# DC-DC_Module_Board_Mk_2.net
KiCad netlist of a schematic drawn in EAGLE
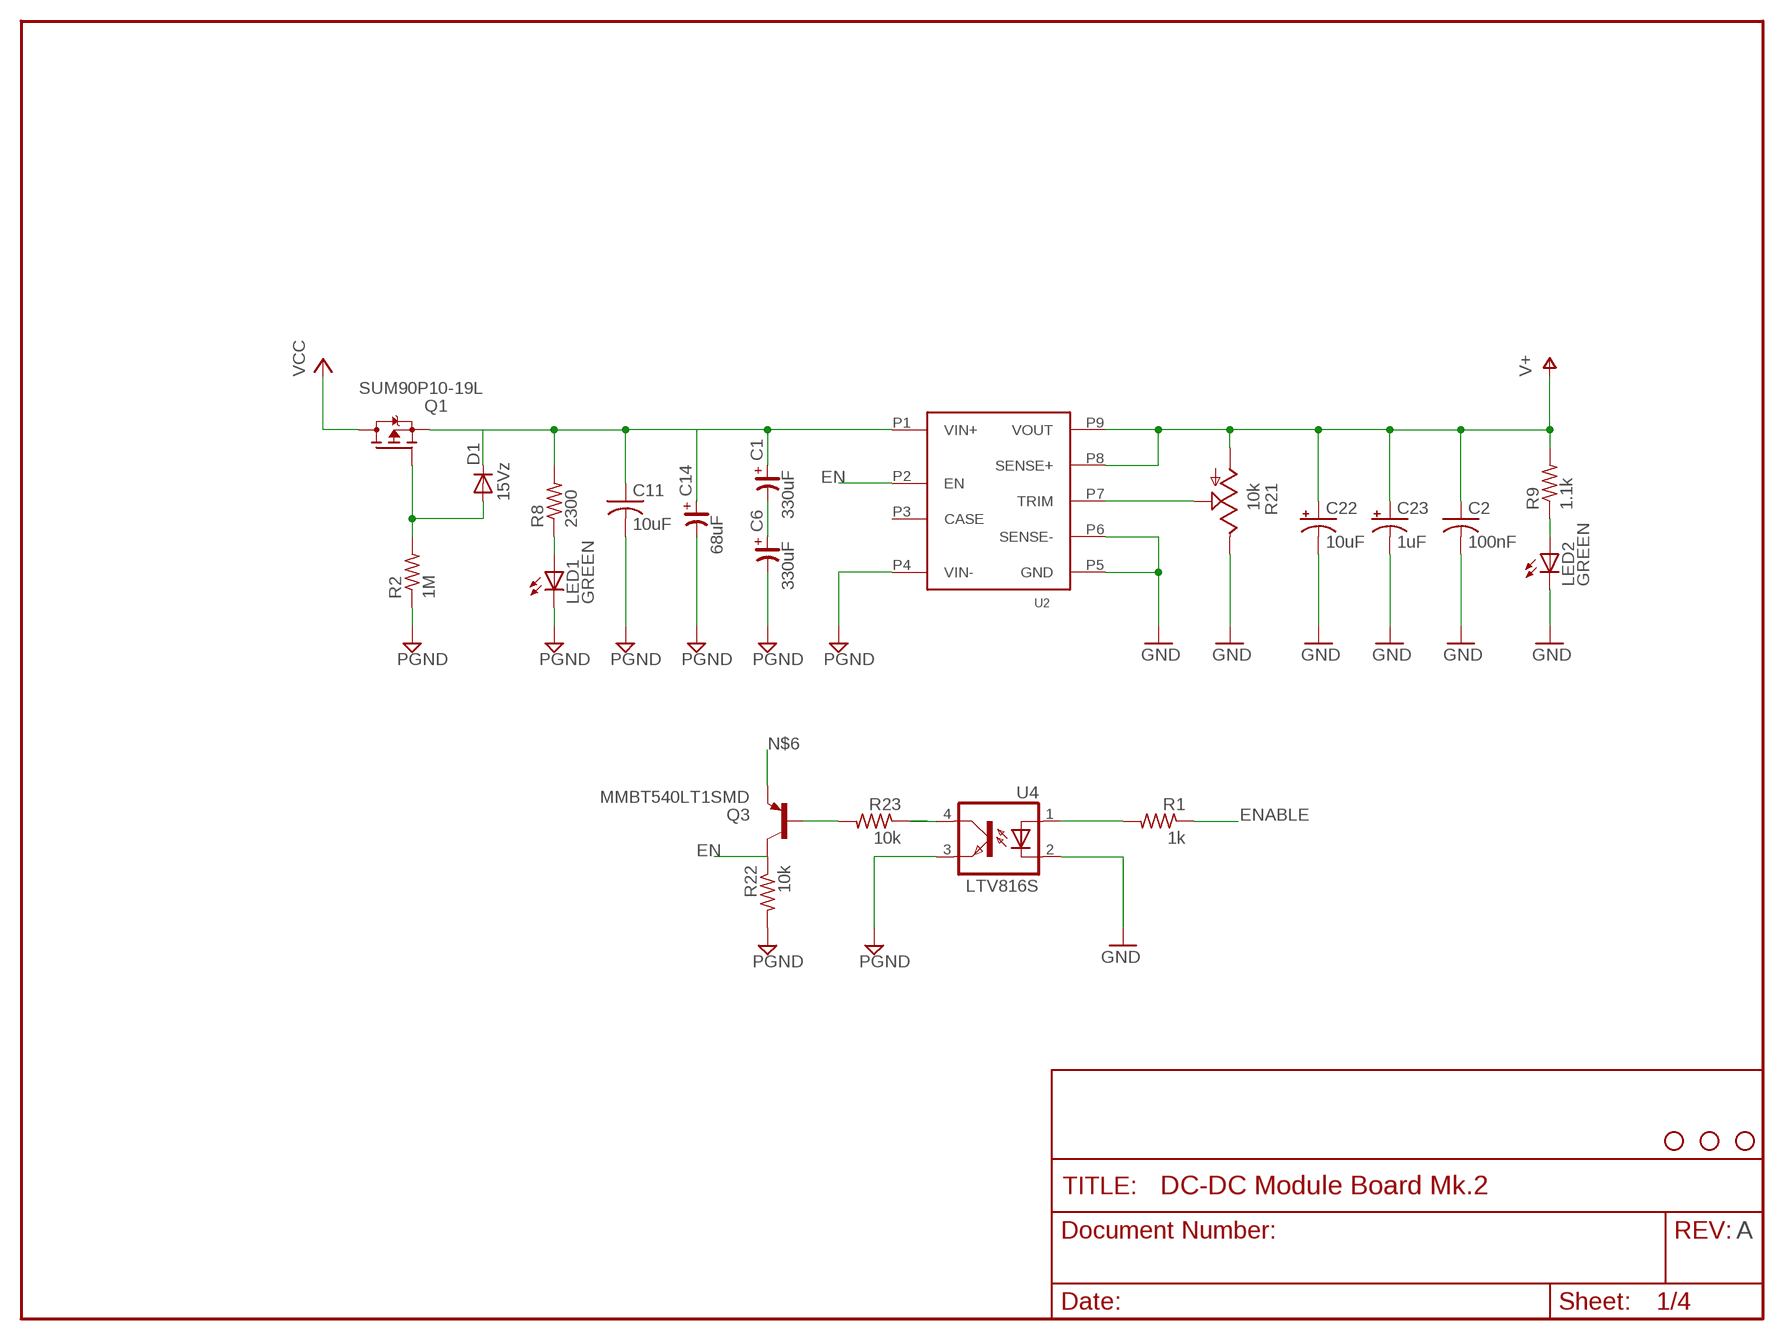
[diagram p0: schematic, sheet 1]
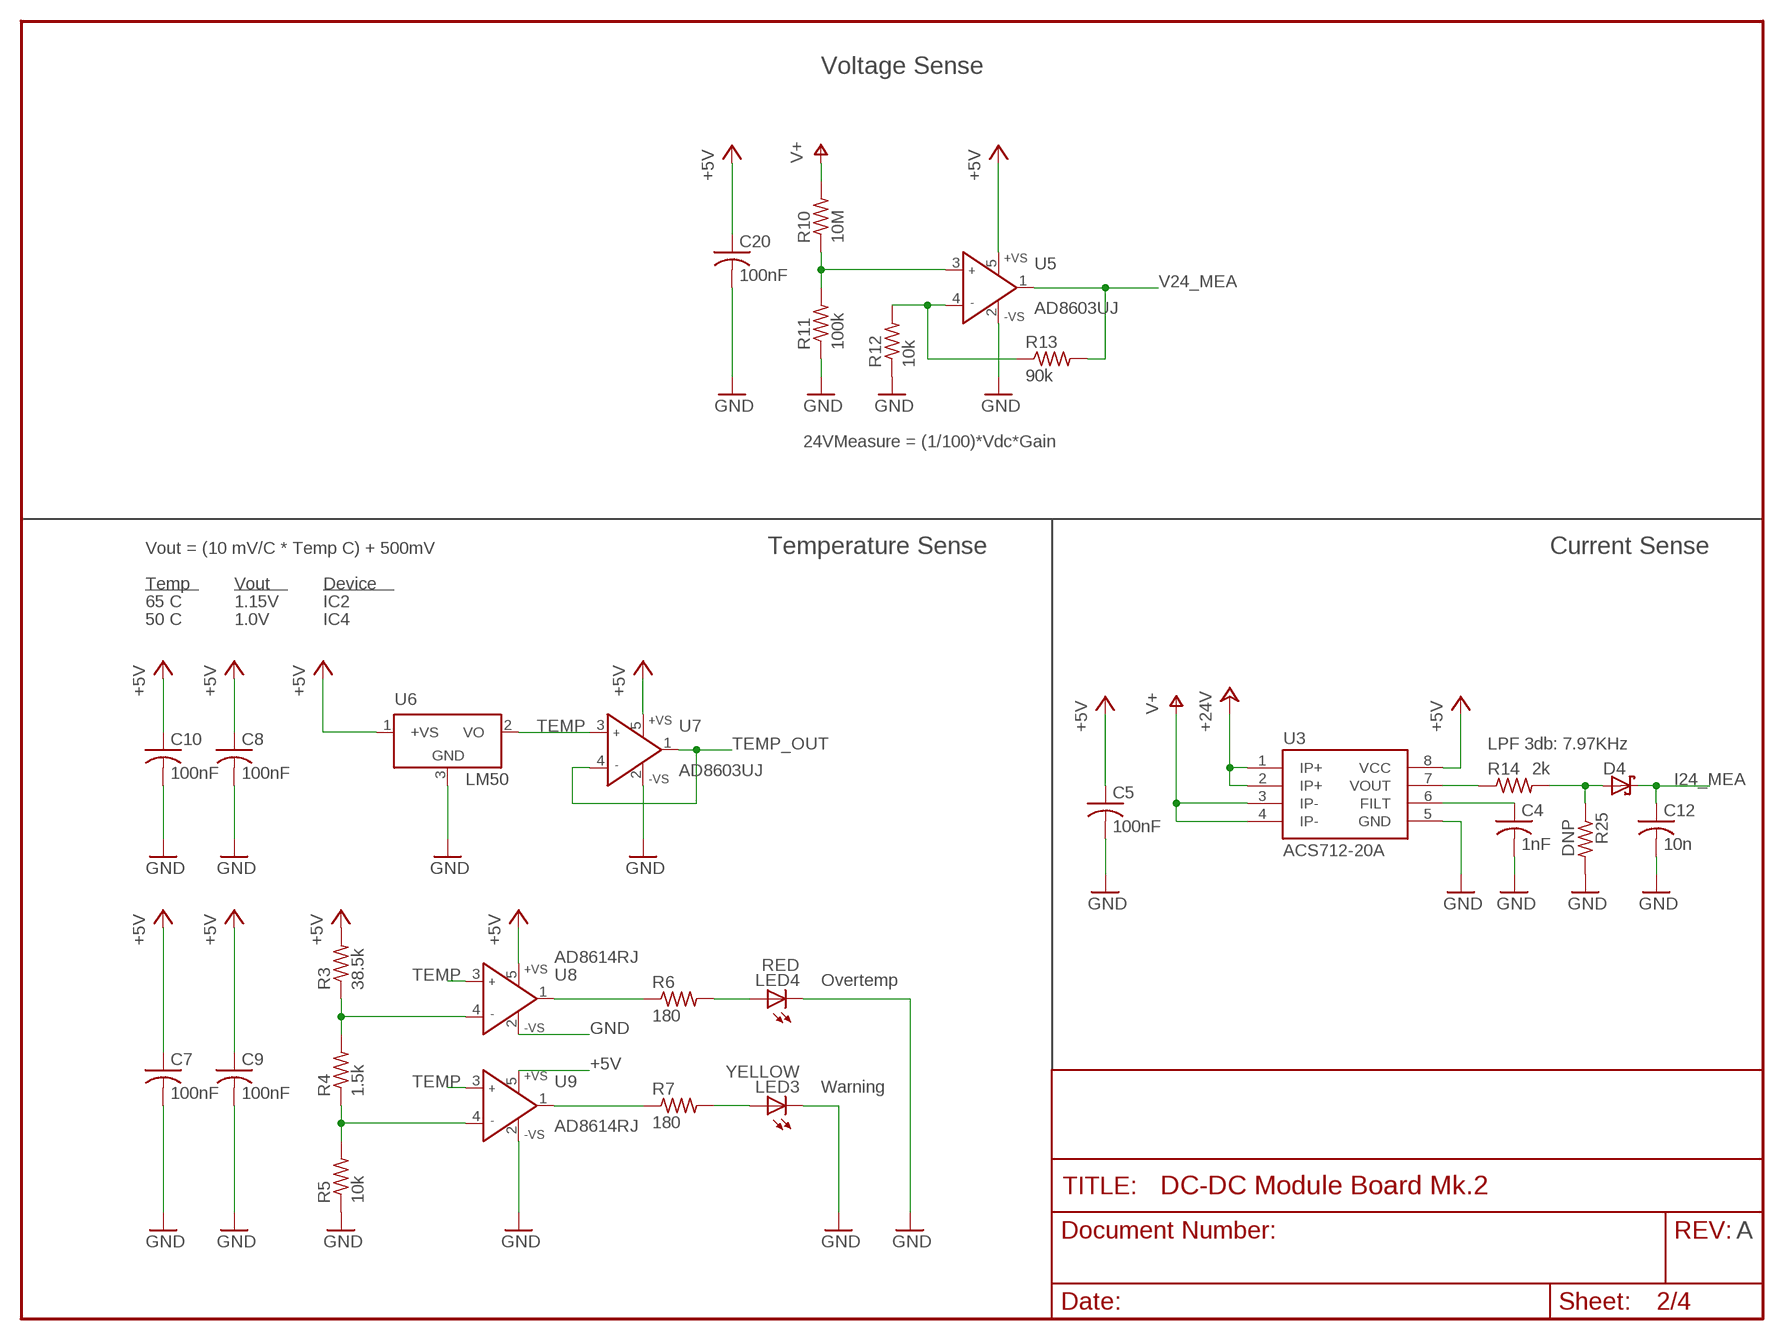
[diagram p1: schematic, sheet 2]
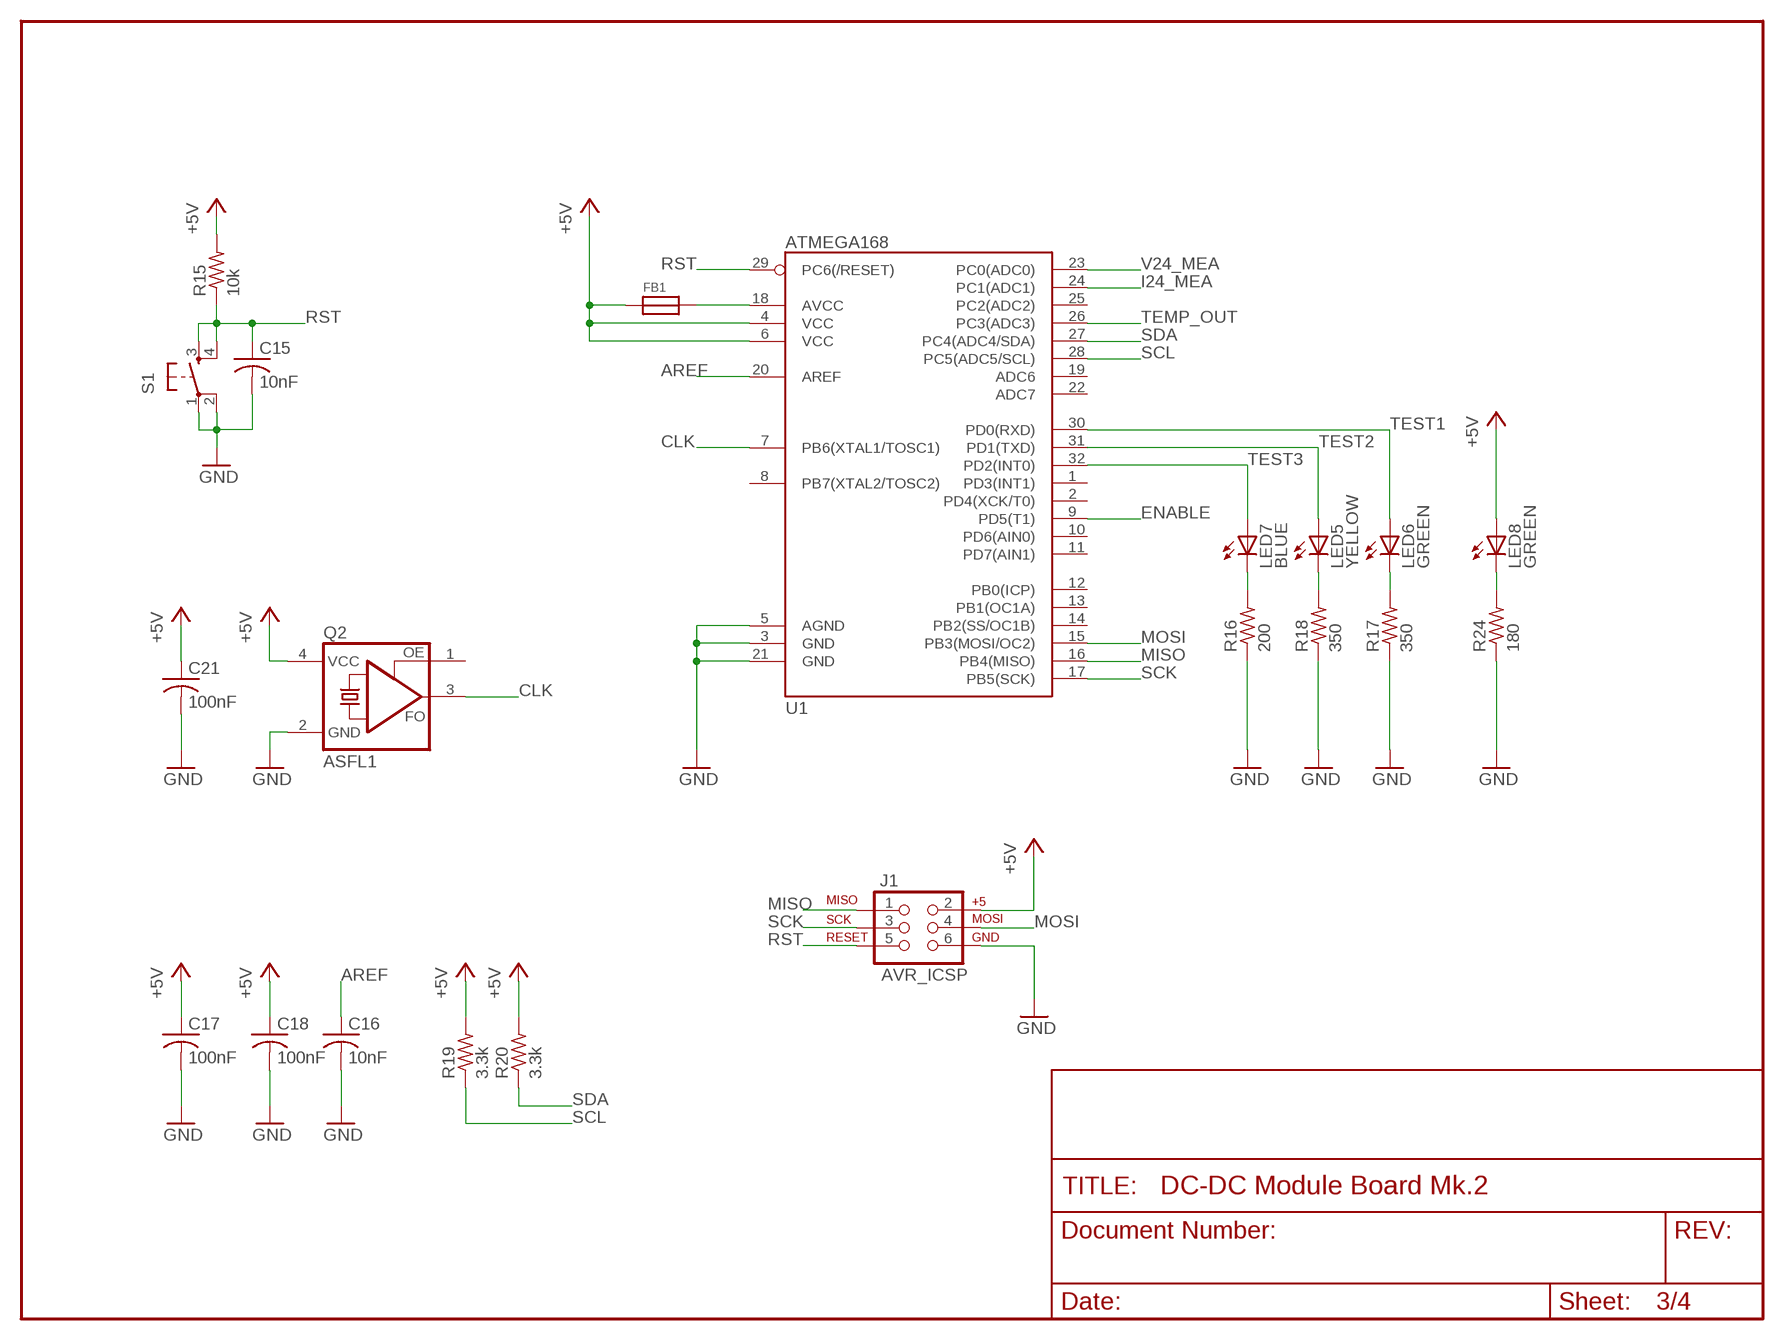
[diagram p2: schematic, sheet 3]
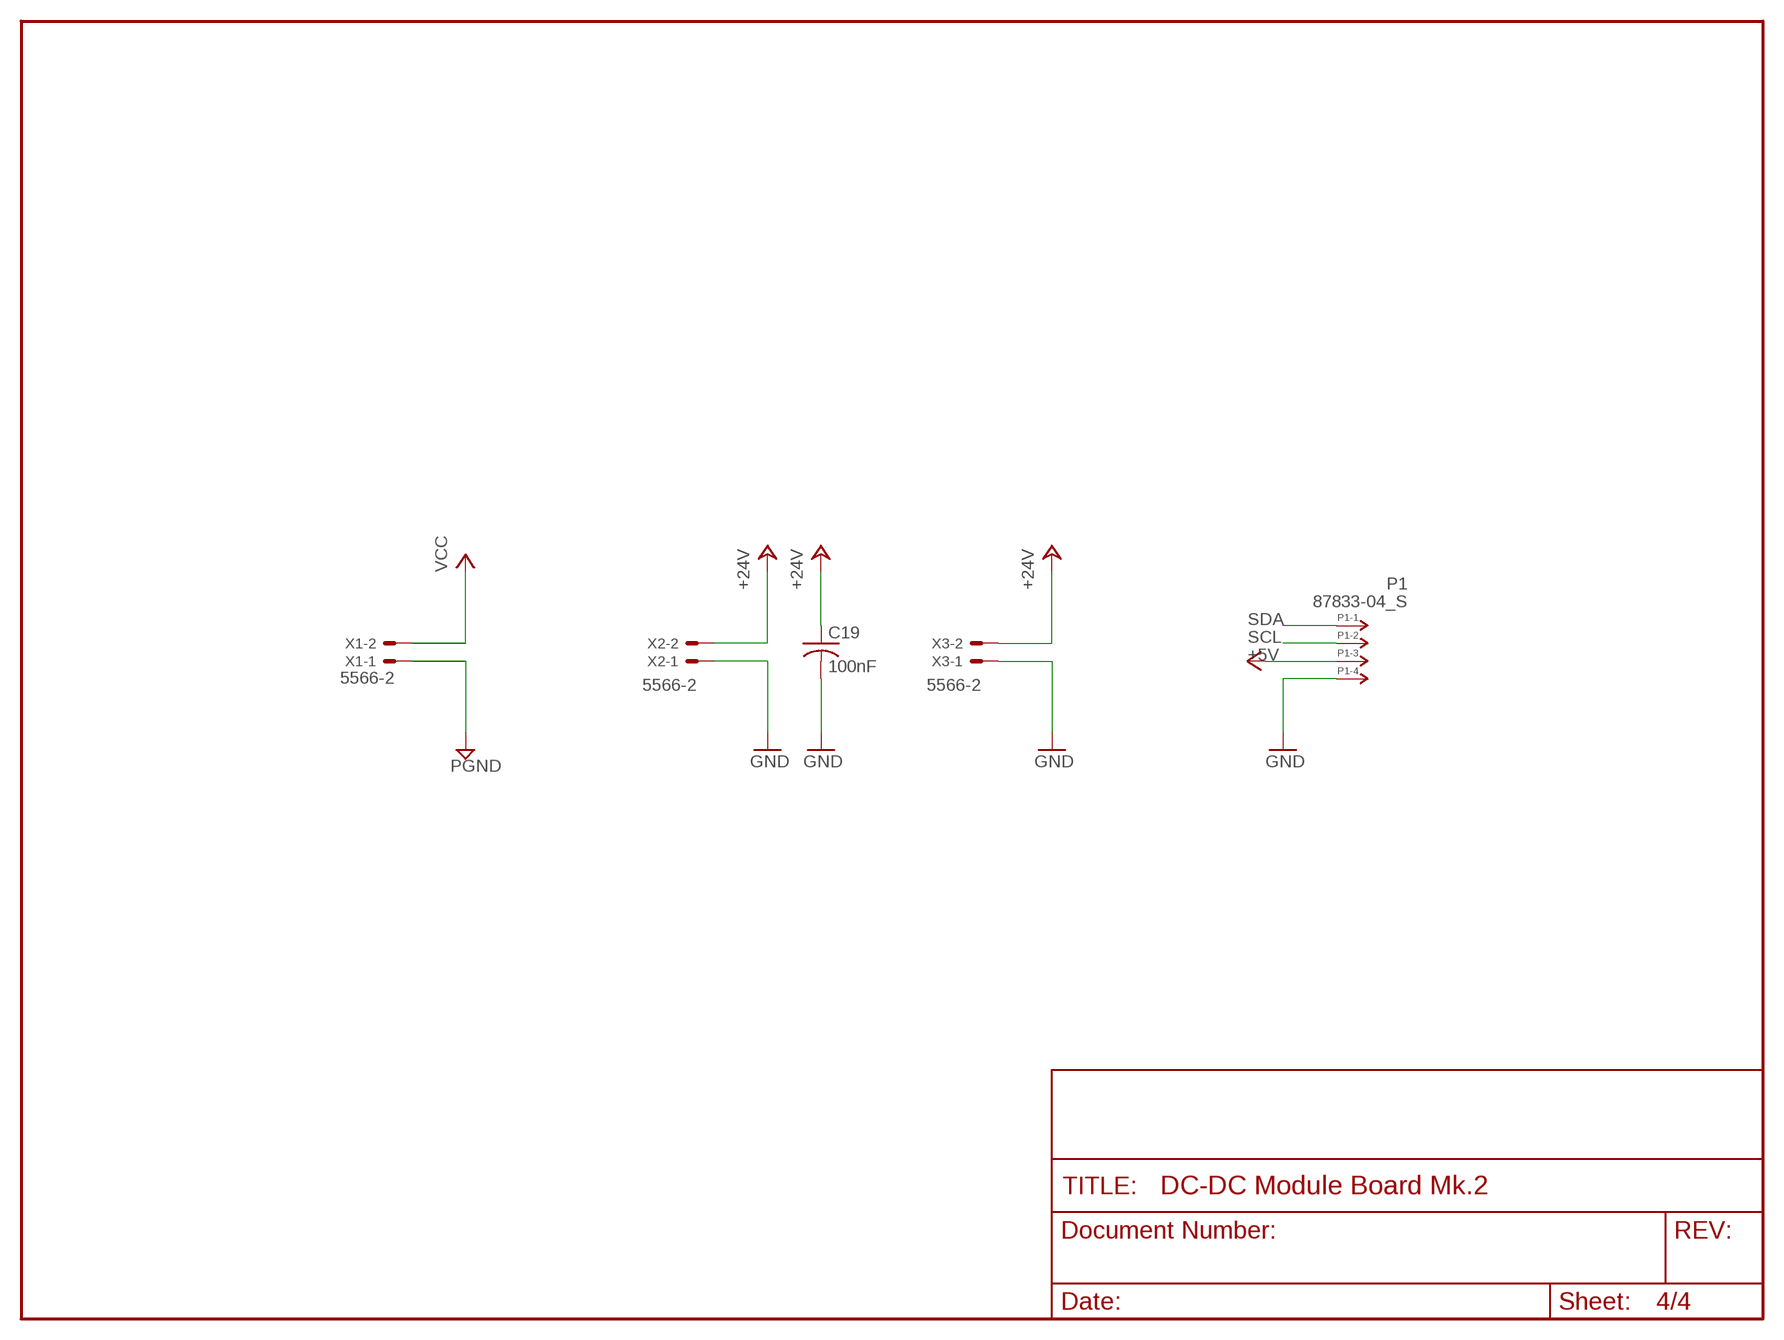
[diagram p3: schematic, sheet 4]

(export (version "E")
  (design (tool "Eeschema 10.0.6"))
  (components
    (comp (ref "C4")
      (value "1nF")
      (footprint "eagle-import:C0603")
      (fields (field (name "PARTNO") "490-1472-1-ND"))
      (libsource (lib "eagle-import") (part "C-USC0603"))
    )
    (comp (ref "C5")
      (value "100nF")
      (footprint "eagle-import:C0603")
      (fields (field (name "PARTNO") "445-5202-1-ND"))
      (libsource (lib "eagle-import") (part "C-USC0603"))
    )
    (comp (ref "C7")
      (value "100nF")
      (footprint "eagle-import:C0603")
      (fields (field (name "PARTNO") "445-5202-1-ND"))
      (libsource (lib "eagle-import") (part "C-USC0603"))
    )
    (comp (ref "C8")
      (value "100nF")
      (footprint "eagle-import:C0603")
      (fields (field (name "PARTNO") "445-5202-1-ND"))
      (libsource (lib "eagle-import") (part "C-USC0603"))
    )
    (comp (ref "C9")
      (value "100nF")
      (footprint "eagle-import:C0603")
      (fields (field (name "PARTNO") "445-5202-1-ND"))
      (libsource (lib "eagle-import") (part "C-USC0603"))
    )
    (comp (ref "C10")
      (value "100nF")
      (footprint "eagle-import:C0603")
      (fields (field (name "PARTNO") "445-5202-1-ND"))
      (libsource (lib "eagle-import") (part "C-USC0603"))
    )
    (comp (ref "C12")
      (value "10n")
      (footprint "eagle-import:C0603")
      (fields (field (name "PARTNO") "445-1304-1-ND"))
      (libsource (lib "eagle-import") (part "C-USC0603"))
    )
    (comp (ref "C20")
      (value "100nF")
      (footprint "eagle-import:C0603")
      (fields (field (name "PARTNO") "445-5202-1-ND"))
      (libsource (lib "eagle-import") (part "C-USC0603"))
    )
    (comp (ref "D4")
      (value "BAT54")
      (footprint "eagle-import:SOT23")
      (fields (field (name "PARTNO") "BAT54FSCT-ND"))
      (libsource (lib "eagle-import") (part "BAT54"))
    )
    (comp (ref "LED3")
      (value "YELLOW")
      (footprint "eagle-import:LED-0603")
      (fields (field (name "PARTNO") "160-1447-1-ND"))
      (libsource (lib "eagle-import") (part "LED0603"))
    )
    (comp (ref "LED4")
      (value "RED")
      (footprint "eagle-import:LED-0603")
      (fields (field (name "PARTNO") "160-1448-1-ND"))
      (libsource (lib "eagle-import") (part "LED0603"))
    )
    (comp (ref "R3")
      (value "38.5k")
      (footprint "eagle-import:R0603")
      (fields (field (name "PARTNO") "P33.2KHCT-ND"))
      (libsource (lib "eagle-import") (part "R-US_R0603"))
    )
    (comp (ref "R4")
      (value "1.5k")
      (footprint "eagle-import:R0603")
      (fields (field (name "PARTNO") "P2.70KHCT-ND"))
      (libsource (lib "eagle-import") (part "R-US_R0603"))
    )
    (comp (ref "R5")
      (value "10k")
      (footprint "eagle-import:R0603")
      (fields (field (name "PARTNO") "P10.0KHCT-ND"))
      (libsource (lib "eagle-import") (part "R-US_R0603"))
    )
    (comp (ref "R6")
      (value "180")
      (footprint "eagle-import:R0603")
      (fields (field (name "PARTNO") "P82.0HCT-ND"))
      (libsource (lib "eagle-import") (part "R-US_R0603"))
    )
    (comp (ref "R7")
      (value "180")
      (footprint "eagle-import:R0603")
      (fields (field (name "PARTNO") "P82.0HCT-ND"))
      (libsource (lib "eagle-import") (part "R-US_R0603"))
    )
    (comp (ref "R10")
      (value "10M")
      (footprint "eagle-import:R0603")
      (fields (field (name "PARTNO") "P10MGCT-ND"))
      (libsource (lib "eagle-import") (part "R-US_R0603"))
    )
    (comp (ref "R11")
      (value "100k")
      (footprint "eagle-import:R0603")
      (fields (field (name "PARTNO") "P100KHCT-ND"))
      (libsource (lib "eagle-import") (part "R-US_R0603"))
    )
    (comp (ref "R12")
      (value "10k")
      (footprint "eagle-import:R0603")
      (fields (field (name "PARTNO") "P10.0KHCT-ND"))
      (libsource (lib "eagle-import") (part "R-US_R0603"))
    )
    (comp (ref "R13")
      (value "90k")
      (footprint "eagle-import:R0603")
      (fields (field (name "PARTNO") "P90.9KHCT-ND"))
      (libsource (lib "eagle-import") (part "R-US_R0603"))
    )
    (comp (ref "R14")
      (value "2k")
      (footprint "eagle-import:R0603")
      (fields (field (name "PARTNO") "P2.00KHCT-ND"))
      (libsource (lib "eagle-import") (part "R-US_R0603"))
    )
    (comp (ref "R25")
      (value "DNP")
      (footprint "eagle-import:R0603")
      (fields (field (name "PARTNO") "P2.00KHCT-ND"))
      (libsource (lib "eagle-import") (part "R-US_R0603"))
    )
    (comp (ref "U3")
      (value "ACS712-20A")
      (footprint "eagle-import:SO08")
      (fields (field (name "PARTNO") "620-1190-1-ND"))
      (libsource (lib "eagle-import") (part "ACS712"))
    )
    (comp (ref "U5")
      (value "AD8603UJ")
      (footprint "eagle-import:SOT23-5")
      (fields
        (field (name "MF") "ALTERA CORPORATION")
        (field (name "MPN") "AD8603AUJZ-REEL7")
        (field (name "PARTNO") "AD8603AUJZREEL7CT-ND")
      )
      (libsource (lib "eagle-import") (part "AD8603UJ"))
    )
    (comp (ref "U6")
      (value "LM50")
      (footprint "eagle-import:SOT23")
      (fields (field (name "PARTNO") "LM50CIM3CT-ND"))
      (libsource (lib "eagle-import") (part "LM50"))
    )
    (comp (ref "U7")
      (value "AD8603UJ")
      (footprint "eagle-import:SOT23-5")
      (fields
        (field (name "MF") "ALTERA CORPORATION")
        (field (name "MPN") "AD8603AUJZ-REEL7")
        (field (name "PARTNO") "AD8603AUJZREEL7CT-ND")
      )
      (libsource (lib "eagle-import") (part "AD8603UJ"))
    )
    (comp (ref "U8")
      (value "AD8614RJ")
      (footprint "eagle-import:SOT23-5")
      (fields
        (field (name "MF") "ALTERA CORPORATION")
        (field (name "MPN") "AD8614ARTZ-REEL7")
        (field (name "PARTNO") "AD8614ARTZ-REEL7CT-ND")
      )
      (libsource (lib "eagle-import") (part "AD8614RJ"))
    )
    (comp (ref "U9")
      (value "AD8614RJ")
      (footprint "eagle-import:SOT23-5")
      (fields
        (field (name "MF") "ALTERA CORPORATION")
        (field (name "MPN") "AD8614ARTZ-REEL7")
        (field (name "PARTNO") "AD8614ARTZ-REEL7CT-ND")
      )
      (libsource (lib "eagle-import") (part "AD8614RJ"))
    )
    (comp (ref "C19")
      (value "100nF")
      (footprint "eagle-import:C0603")
      (fields (field (name "PARTNO") "445-5202-1-ND"))
      (libsource (lib "eagle-import") (part "C-USC0603"))
    )
    (comp (ref "P1")
      (value "87833-04_S")
      (footprint "eagle-import:87833-04")
      (fields (field (name "PARTNO") "WM18858-ND") (field (name "BOM") "INCLUDE"))
      (libsource (lib "eagle-import") (part "87833-04_S"))
    )
    (comp (ref "X1")
      (value "5566-2")
      (footprint "eagle-import:5566-2")
      (fields
        (field (name "OC_FARNELL") "1822072")
        (field (name "OC_NEWARK") "unknown")
        (field (name "PARTNO") "WM23800-ND")
        (field (name "BOM") "INCLUDE")
      )
      (libsource (lib "eagle-import") (part "5566-2"))
    )
    (comp (ref "X2")
      (value "5566-2")
      (footprint "eagle-import:5566-2")
      (fields (field (name "PARTNO") "WM23800-ND") (field (name "BOM") "INCLUDE"))
      (libsource (lib "eagle-import") (part "5566-2"))
    )
    (comp (ref "X3")
      (value "5566-2")
      (footprint "eagle-import:5566-2")
      (fields
        (field (name "OC_FARNELL") "1822072")
        (field (name "OC_NEWARK") "unknown")
        (field (name "PARTNO") "WM23800-ND")
        (field (name "BOM") "INCLUDE")
      )
      (libsource (lib "eagle-import") (part "5566-2"))
    )
    (comp (ref "C15")
      (value "10nF")
      (footprint "eagle-import:C0603")
      (fields (field (name "PARTNO") "445-1304-1-ND"))
      (libsource (lib "eagle-import") (part "C-USC0603"))
    )
    (comp (ref "C16")
      (value "10nF")
      (footprint "eagle-import:C0603")
      (fields (field (name "PARTNO") "445-1304-1-ND"))
      (libsource (lib "eagle-import") (part "C-USC0603"))
    )
    (comp (ref "C17")
      (value "100nF")
      (footprint "eagle-import:C0603")
      (fields (field (name "PARTNO") "445-5202-1-ND"))
      (libsource (lib "eagle-import") (part "C-USC0603"))
    )
    (comp (ref "C18")
      (value "100nF")
      (footprint "eagle-import:C0603")
      (fields (field (name "PARTNO") "445-5202-1-ND"))
      (libsource (lib "eagle-import") (part "C-USC0603"))
    )
    (comp (ref "C21")
      (value "100nF")
      (footprint "eagle-import:C0603")
      (fields (field (name "PARTNO") "445-5047-1-ND"))
      (libsource (lib "eagle-import") (part "C-USC0603"))
    )
    (comp (ref "FB1")
      (value "FERRITE")
      (footprint "eagle-import:0603")
      (fields (field (name "PARTNO") "445-2164-1-ND"))
      (libsource (lib "eagle-import") (part "FERRITE"))
    )
    (comp (ref "J1")
      (value "AVR_ICSP")
      (footprint "eagle-import:2X3_LOCK")
      (libsource (lib "eagle-import") (part "AVR_SPI_PRG_62X3_LOCK"))
    )
    (comp (ref "LED5")
      (value "YELLOW")
      (footprint "eagle-import:LED-0603")
      (fields (field (name "PARTNO") "160-1448-1-ND"))
      (libsource (lib "eagle-import") (part "LED0603"))
    )
    (comp (ref "LED6")
      (value "GREEN")
      (footprint "eagle-import:LED-0603")
      (fields (field (name "PARTNO") "160-1446-1-ND"))
      (libsource (lib "eagle-import") (part "LED0603"))
    )
    (comp (ref "LED7")
      (value "BLUE")
      (footprint "eagle-import:LED-0603")
      (fields (field (name "PARTNO") "160-1647-1-ND"))
      (libsource (lib "eagle-import") (part "LED0603"))
    )
    (comp (ref "LED8")
      (value "GREEN")
      (footprint "eagle-import:LED-0603")
      (fields (field (name "PARTNO") "160-1446-1-ND"))
      (libsource (lib "eagle-import") (part "LED0603"))
    )
    (comp (ref "Q2")
      (value "ASFL1")
      (footprint "eagle-import:ASF")
      (fields
        (field (name "MF") "Abracon Corporation")
        (field (name "MPN") "ASFL1-125.000MHZ-EC-T")
        (field (name "PARTNO") "XC1900CT-ND")
      )
      (libsource (lib "eagle-import") (part "ASFL1"))
    )
    (comp (ref "R15")
      (value "10k")
      (footprint "eagle-import:R0603")
      (fields (field (name "PARTNO") "P10.0KHCT-ND"))
      (libsource (lib "eagle-import") (part "R-US_R0603"))
    )
    (comp (ref "R16")
      (value "200")
      (footprint "eagle-import:R0603")
      (fields (field (name "PARTNO") "P200HCT-ND"))
      (libsource (lib "eagle-import") (part "R-US_R0603"))
    )
    (comp (ref "R17")
      (value "350")
      (footprint "eagle-import:R0603")
      (fields (field (name "PARTNO") "P340HCT-ND"))
      (libsource (lib "eagle-import") (part "R-US_R0603"))
    )
    (comp (ref "R18")
      (value "350")
      (footprint "eagle-import:R0603")
      (fields (field (name "PARTNO") "P340HCT-ND"))
      (libsource (lib "eagle-import") (part "R-US_R0603"))
    )
    (comp (ref "R19")
      (value "3.3k")
      (footprint "eagle-import:R0603")
      (fields (field (name "PARTNO") "P33.0KHCT-ND"))
      (libsource (lib "eagle-import") (part "R-US_R0603"))
    )
    (comp (ref "R20")
      (value "3.3k")
      (footprint "eagle-import:R0603")
      (fields (field (name "PARTNO") "P33.0KHCT-ND"))
      (libsource (lib "eagle-import") (part "R-US_R0603"))
    )
    (comp (ref "R24")
      (value "180")
      (footprint "eagle-import:R0603")
      (fields (field (name "PARTNO") "P180HCT-ND"))
      (libsource (lib "eagle-import") (part "R-US_R0603"))
    )
    (comp (ref "S1")
      (value "TAC_SWITCHSMD")
      (footprint "eagle-import:TACTILE_SWITCH_SMD")
      (fields (field (name "PARTNO") "COM-08720"))
      (libsource (lib "eagle-import") (part "TAC_SWITCHSMD"))
    )
    (comp (ref "U1")
      (value "ATMEGA168")
      (footprint "eagle-import:TQFP32-08")
      (fields (field (name "PARTNO") "ATMEGA168-20AU-ND"))
      (libsource (lib "eagle-import") (part "ATMEGA168"))
    )
    (comp (ref "C1")
      (value "330uF")
      (footprint "eagle-import:CSV-H")
      (fields (field (name "PARTNO") "338-2190-1-ND"))
      (libsource (lib "eagle-import") (part "CP_SV-H"))
    )
    (comp (ref "C2")
      (value "100nF")
      (footprint "eagle-import:C0603")
      (fields (field (name "PARTNO") "445-5202-1-ND"))
      (libsource (lib "eagle-import") (part "C-USC0603"))
    )
    (comp (ref "C6")
      (value "330uF")
      (footprint "eagle-import:CSV-H")
      (fields (field (name "PARTNO") "338-2190-1-ND"))
      (libsource (lib "eagle-import") (part "CP_SV-H"))
    )
    (comp (ref "C11")
      (value "10uF")
      (footprint "eagle-import:C2220K")
      (fields (field (name "PARTNO") "445-5212-1-ND"))
      (libsource (lib "eagle-import") (part "C-USC2220K"))
    )
    (comp (ref "C14")
      (value "68uF")
      (footprint "eagle-import:CSV-H")
      (fields (field (name "PARTNO") "565-2343-1-ND"))
      (libsource (lib "eagle-import") (part "CP_SV-H"))
    )
    (comp (ref "C22")
      (value "10uF")
      (footprint "eagle-import:EIA7343")
      (fields (field (name "PARTNO") "399-3893-1-ND"))
      (libsource (lib "eagle-import") (part "CAP_POL7343"))
    )
    (comp (ref "C23")
      (value "1uF")
      (footprint "eagle-import:EIA3528")
      (fields (field (name "PARTNO") "478-6247-1-ND"))
      (libsource (lib "eagle-import") (part "CAP_POL3528"))
    )
    (comp (ref "D1")
      (value "15Vz")
      (footprint "eagle-import:SOD123")
      (fields (field (name "PARTNO") "MMSZ5245BFSCT-ND"))
      (libsource (lib "eagle-import") (part "DIODE-SOD123"))
    )
    (comp (ref "JP1")
      (value "STAND-OFF")
      (footprint "eagle-import:STAND-OFF")
      (libsource (lib "eagle-import") (part "STAND-OFF"))
    )
    (comp (ref "JP2")
      (value "STAND-OFF")
      (footprint "eagle-import:STAND-OFF")
      (libsource (lib "eagle-import") (part "STAND-OFF"))
    )
    (comp (ref "JP4")
      (value "STAND-OFF")
      (footprint "eagle-import:STAND-OFF")
      (libsource (lib "eagle-import") (part "STAND-OFF"))
    )
    (comp (ref "LED1")
      (value "GREEN")
      (footprint "eagle-import:LED-0603")
      (fields (field (name "PARTNO") "160-1446-1-ND"))
      (libsource (lib "eagle-import") (part "LED0603"))
    )
    (comp (ref "LED2")
      (value "GREEN")
      (footprint "eagle-import:LED-0603")
      (fields (field (name "PARTNO") "160-1446-1-ND"))
      (libsource (lib "eagle-import") (part "LED0603"))
    )
    (comp (ref "Q1")
      (value "SUM90P10-19L")
      (footprint "eagle-import:TO263")
      (fields (field (name "PARTNO") "SUM90P10-19L-E3CT-ND"))
      (libsource (lib "eagle-import") (part "SPB80P06P"))
    )
    (comp (ref "Q3")
      (value "MMBT540LT1SMD")
      (footprint "eagle-import:SOT23-BEC")
      (fields (field (name "PARTNO") "MMBT5401FSCT-ND"))
      (libsource (lib "eagle-import") (part "MMBT540SMDLT1"))
    )
    (comp (ref "R1")
      (value "1k")
      (footprint "eagle-import:R0603")
      (fields (field (name "PARTNO") "P1.00KHCT-ND"))
      (libsource (lib "eagle-import") (part "R-US_R0603"))
    )
    (comp (ref "R2")
      (value "1M")
      (footprint "eagle-import:R0603")
      (fields (field (name "PARTNO") "1.00MHCT-ND"))
      (libsource (lib "eagle-import") (part "R-US_R0603"))
    )
    (comp (ref "R8")
      (value "2300")
      (footprint "eagle-import:R2512")
      (fields (field (name "PARTNO") "RHC2512FT2K20CT-ND"))
      (libsource (lib "eagle-import") (part "R-US_R2512"))
    )
    (comp (ref "R9")
      (value "1.1k")
      (footprint "eagle-import:R1206")
      (fields (field (name "PARTNO") "RNCP1206FTD1K10CT-ND"))
      (libsource (lib "eagle-import") (part "R-US_R1206"))
    )
    (comp (ref "R21")
      (value "10k")
      (footprint "eagle-import:SM-42_43W")
      (fields (field (name "PARTNO") "SM-43TW103CT-ND"))
      (libsource (lib "eagle-import") (part "TRIM_US-SM-42/43W"))
    )
    (comp (ref "R22")
      (value "10k")
      (footprint "eagle-import:R0603")
      (fields (field (name "PARTNO") "P10.0KHCT-ND"))
      (libsource (lib "eagle-import") (part "R-US_R0603"))
    )
    (comp (ref "R23")
      (value "10k")
      (footprint "eagle-import:R0603")
      (fields (field (name "PARTNO") "P10.0KHCT-ND"))
      (libsource (lib "eagle-import") (part "R-US_R0603"))
    )
    (comp (ref "U2")
      (value "CHB350-24V")
      (footprint "eagle-import:CHB350HALFBRICK")
      (libsource (lib "eagle-import") (part "CHB350-24V"))
    )
    (comp (ref "U4")
      (value "LTV816S")
      (footprint "eagle-import:SMD4")
      (fields (field (name "PARTNO") "160-1361-5-ND"))
      (libsource (lib "eagle-import") (part "LTV816S"))
    )
  )
  (nets
    (net (code "1") (name "+5V") (class "Default")
      (node (ref "C10") (pin "1") (pinfunction "1_1") (pintype "passive"))
      (node (ref "C17") (pin "1") (pinfunction "1_1") (pintype "passive"))
      (node (ref "C18") (pin "1") (pinfunction "1_1") (pintype "passive"))
      (node (ref "C20") (pin "1") (pinfunction "1_1") (pintype "passive"))
      (node (ref "C21") (pin "1") (pinfunction "1_1") (pintype "passive"))
      (node (ref "C5") (pin "1") (pinfunction "1_1") (pintype "passive"))
      (node (ref "C7") (pin "1") (pinfunction "1_1") (pintype "passive"))
      (node (ref "C8") (pin "1") (pinfunction "1_1") (pintype "passive"))
      (node (ref "C9") (pin "1") (pinfunction "1_1") (pintype "passive"))
      (node (ref "FB1") (pin "1") (pinfunction "P$1_1") (pintype "bidirectional"))
      (node (ref "J1") (pin "2") (pinfunction "2_2") (pintype "passive"))
      (node (ref "LED8") (pin "A") (pinfunction "A_A") (pintype "passive"))
      (node (ref "P1") (pin "3") (pinfunction "P_3") (pintype "passive"))
      (node (ref "Q2") (pin "4") (pinfunction "VCC_4") (pintype "power_in"))
      (node (ref "R15") (pin "2") (pinfunction "2_2") (pintype "passive"))
      (node (ref "R19") (pin "2") (pinfunction "2_2") (pintype "passive"))
      (node (ref "R20") (pin "2") (pinfunction "2_2") (pintype "passive"))
      (node (ref "R3") (pin "2") (pinfunction "2_2") (pintype "passive"))
      (node (ref "U1") (pin "4") (pinfunction "VCC_4") (pintype "bidirectional"))
      (node (ref "U1") (pin "6") (pinfunction "VCC_6") (pintype "bidirectional"))
      (node (ref "U3") (pin "8") (pinfunction "VCC_8") (pintype "bidirectional"))
      (node (ref "U5") (pin "5") (pinfunction "+VS_5") (pintype "input"))
      (node (ref "U6") (pin "1") (pinfunction "+VS_1") (pintype "input"))
      (node (ref "U7") (pin "5") (pinfunction "+VS_5") (pintype "input"))
      (node (ref "U8") (pin "5") (pinfunction "+VS_5") (pintype "input"))
      (node (ref "U9") (pin "5") (pinfunction "+VS_5") (pintype "input"))
    )
    (net (code "2") (name "+24V") (class "Default")
      (node (ref "C19") (pin "1") (pinfunction "1_1") (pintype "passive"))
      (node (ref "U3") (pin "1") (pinfunction "IP+_1") (pintype "bidirectional"))
      (node (ref "U3") (pin "2") (pinfunction "IP+_2") (pintype "bidirectional"))
      (node (ref "X2") (pin "2") (pinfunction "S_2") (pintype "passive"))
      (node (ref "X3") (pin "2") (pinfunction "S_2") (pintype "passive"))
    )
    (net (code "3") (name "AREF") (class "Default")
      (node (ref "C16") (pin "1") (pinfunction "1_1") (pintype "passive"))
      (node (ref "U1") (pin "20") (pinfunction "AREF_20") (pintype "bidirectional"))
    )
    (net (code "4") (name "CLK") (class "Default")
      (node (ref "Q2") (pin "3") (pinfunction "FO_3") (pintype "output"))
      (node (ref "U1") (pin "7") (pinfunction "PB6(XTAL1/TOSC1)_7") (pintype "bidirectional"))
    )
    (net (code "5") (name "EN") (class "Default")
      (node (ref "Q3") (pin "C") (pinfunction "C_C") (pintype "passive"))
      (node (ref "R22") (pin "1") (pinfunction "1_1") (pintype "passive"))
      (node (ref "U2") (pin "P2") (pinfunction "EN_P2") (pintype "bidirectional"))
    )
    (net (code "6") (name "ENABLE") (class "Default")
      (node (ref "R1") (pin "1") (pinfunction "1_1") (pintype "passive"))
      (node (ref "U1") (pin "9") (pinfunction "PD5(T1)_9") (pintype "bidirectional"))
    )
    (net (code "7") (name "GND") (class "Default")
      (node (ref "C10") (pin "2") (pinfunction "2_2") (pintype "passive"))
      (node (ref "C12") (pin "2") (pinfunction "2_2") (pintype "passive"))
      (node (ref "C15") (pin "2") (pinfunction "2_2") (pintype "passive"))
      (node (ref "C16") (pin "2") (pinfunction "2_2") (pintype "passive"))
      (node (ref "C17") (pin "2") (pinfunction "2_2") (pintype "passive"))
      (node (ref "C18") (pin "2") (pinfunction "2_2") (pintype "passive"))
      (node (ref "C19") (pin "2") (pinfunction "2_2") (pintype "passive"))
      (node (ref "C2") (pin "2") (pinfunction "2_2") (pintype "passive"))
      (node (ref "C20") (pin "2") (pinfunction "2_2") (pintype "passive"))
      (node (ref "C21") (pin "2") (pinfunction "2_2") (pintype "passive"))
      (node (ref "C22") (pin "C") (pinfunction "-_C") (pintype "passive"))
      (node (ref "C23") (pin "C") (pinfunction "-_C") (pintype "passive"))
      (node (ref "C4") (pin "2") (pinfunction "2_2") (pintype "passive"))
      (node (ref "C5") (pin "2") (pinfunction "2_2") (pintype "passive"))
      (node (ref "C7") (pin "2") (pinfunction "2_2") (pintype "passive"))
      (node (ref "C8") (pin "2") (pinfunction "2_2") (pintype "passive"))
      (node (ref "C9") (pin "2") (pinfunction "2_2") (pintype "passive"))
      (node (ref "J1") (pin "6") (pinfunction "6_6") (pintype "passive"))
      (node (ref "LED2") (pin "C") (pinfunction "C_C") (pintype "passive"))
      (node (ref "LED3") (pin "C") (pinfunction "C_C") (pintype "passive"))
      (node (ref "LED4") (pin "C") (pinfunction "C_C") (pintype "passive"))
      (node (ref "P1") (pin "4") (pinfunction "P_4") (pintype "passive"))
      (node (ref "Q2") (pin "2") (pinfunction "GND_2") (pintype "power_in"))
      (node (ref "R11") (pin "1") (pinfunction "1_1") (pintype "passive"))
      (node (ref "R12") (pin "1") (pinfunction "1_1") (pintype "passive"))
      (node (ref "R16") (pin "1") (pinfunction "1_1") (pintype "passive"))
      (node (ref "R17") (pin "1") (pinfunction "1_1") (pintype "passive"))
      (node (ref "R18") (pin "1") (pinfunction "1_1") (pintype "passive"))
      (node (ref "R21") (pin "3") (pinfunction "E_3") (pintype "passive"))
      (node (ref "R24") (pin "1") (pinfunction "1_1") (pintype "passive"))
      (node (ref "R25") (pin "2") (pinfunction "2_2") (pintype "passive"))
      (node (ref "R5") (pin "1") (pinfunction "1_1") (pintype "passive"))
      (node (ref "S1") (pin "1") (pinfunction "1_1") (pintype "passive"))
      (node (ref "S1") (pin "2") (pinfunction "2_2") (pintype "passive"))
      (node (ref "U1") (pin "21") (pinfunction "GND_21") (pintype "bidirectional"))
      (node (ref "U1") (pin "3") (pinfunction "GND_3") (pintype "bidirectional"))
      (node (ref "U1") (pin "5") (pinfunction "AGND_5") (pintype "bidirectional"))
      (node (ref "U2") (pin "P5") (pinfunction "GND_P5") (pintype "power_in"))
      (node (ref "U2") (pin "P6") (pinfunction "SENSE-_P6") (pintype "bidirectional"))
      (node (ref "U3") (pin "5") (pinfunction "GND_5") (pintype "bidirectional"))
      (node (ref "U4") (pin "2") (pinfunction "C_2") (pintype "passive"))
      (node (ref "U5") (pin "2") (pinfunction "-VS_2") (pintype "input"))
      (node (ref "U6") (pin "3") (pinfunction "GND_3") (pintype "power_in"))
      (node (ref "U7") (pin "2") (pinfunction "-VS_2") (pintype "input"))
      (node (ref "U8") (pin "2") (pinfunction "-VS_2") (pintype "input"))
      (node (ref "U9") (pin "2") (pinfunction "-VS_2") (pintype "input"))
      (node (ref "X2") (pin "1") (pinfunction "S_1") (pintype "passive"))
      (node (ref "X3") (pin "1") (pinfunction "S_1") (pintype "passive"))
    )
    (net (code "8") (name "GND1") (class "Default")
      (node (ref "C11") (pin "2") (pinfunction "2_2") (pintype "passive"))
      (node (ref "C14") (pin "-") (pinfunction "-_-") (pintype "passive"))
      (node (ref "C6") (pin "-") (pinfunction "-_-") (pintype "passive"))
      (node (ref "LED1") (pin "C") (pinfunction "C_C") (pintype "passive"))
      (node (ref "R2") (pin "1") (pinfunction "1_1") (pintype "passive"))
      (node (ref "R22") (pin "2") (pinfunction "2_2") (pintype "passive"))
      (node (ref "U2") (pin "P4") (pinfunction "VIN-_P4") (pintype "power_in"))
      (node (ref "U4") (pin "3") (pinfunction "EMIT_3") (pintype "passive"))
      (node (ref "X1") (pin "1") (pinfunction "S_1") (pintype "passive"))
    )
    (net (code "9") (name "I24_MEA") (class "Default")
      (node (ref "C12") (pin "1") (pinfunction "1_1") (pintype "passive"))
      (node (ref "D4") (pin "3") (pinfunction "C_3") (pintype "passive"))
      (node (ref "U1") (pin "24") (pinfunction "PC1(ADC1)_24") (pintype "bidirectional"))
    )
    (net (code "10") (name "MISO") (class "Default")
      (node (ref "J1") (pin "1") (pinfunction "1_1") (pintype "passive"))
      (node (ref "U1") (pin "16") (pinfunction "PB4(MISO)_16") (pintype "bidirectional"))
    )
    (net (code "11") (name "MOSI") (class "Default")
      (node (ref "J1") (pin "4") (pinfunction "4_4") (pintype "passive"))
      (node (ref "U1") (pin "15") (pinfunction "PB3(MOSI/OC2)_15") (pintype "bidirectional"))
    )
    (net (code "12") (name "N$6") (class "Default")
      (node (ref "C1") (pin "+") (pinfunction "+_+") (pintype "passive"))
      (node (ref "C11") (pin "1") (pinfunction "1_1") (pintype "passive"))
      (node (ref "C14") (pin "+") (pinfunction "+_+") (pintype "passive"))
      (node (ref "D1") (pin "C") (pinfunction "C_C") (pintype "passive"))
      (node (ref "Q1") (pin "2") (pinfunction "S_2") (pintype "passive"))
      (node (ref "Q3") (pin "E") (pinfunction "E_E") (pintype "passive"))
      (node (ref "R8") (pin "2") (pinfunction "2_2") (pintype "passive"))
      (node (ref "U2") (pin "P1") (pinfunction "VIN+_P1") (pintype "power_in"))
    )
    (net (code "13") (name "Net-(C1-Pad-)") (class "Default")
      (node (ref "C1") (pin "-") (pinfunction "-_-") (pintype "passive"))
      (node (ref "C6") (pin "+") (pinfunction "+_+") (pintype "passive"))
    )
    (net (code "14") (name "Net-(D4-A)") (class "Default")
      (node (ref "D4") (pin "1") (pinfunction "A_1") (pintype "passive"))
      (node (ref "R14") (pin "2") (pinfunction "2_2") (pintype "passive"))
      (node (ref "R25") (pin "1") (pinfunction "1_1") (pintype "passive"))
    )
    (net (code "15") (name "Net-(FB1-P$2)") (class "Default")
      (node (ref "FB1") (pin "2") (pinfunction "P$2_2") (pintype "bidirectional"))
      (node (ref "U1") (pin "18") (pinfunction "AVCC_18") (pintype "bidirectional"))
    )
    (net (code "16") (name "Net-(LED1-PadA)") (class "Default")
      (node (ref "LED1") (pin "A") (pinfunction "A_A") (pintype "passive"))
      (node (ref "R8") (pin "1") (pinfunction "1_1") (pintype "passive"))
    )
    (net (code "17") (name "Net-(LED2-PadA)") (class "Default")
      (node (ref "LED2") (pin "A") (pinfunction "A_A") (pintype "passive"))
      (node (ref "R9") (pin "1") (pinfunction "1_1") (pintype "passive"))
    )
    (net (code "18") (name "Net-(LED3-PadA)") (class "Default")
      (node (ref "LED3") (pin "A") (pinfunction "A_A") (pintype "passive"))
      (node (ref "R7") (pin "2") (pinfunction "2_2") (pintype "passive"))
    )
    (net (code "19") (name "Net-(LED4-PadA)") (class "Default")
      (node (ref "LED4") (pin "A") (pinfunction "A_A") (pintype "passive"))
      (node (ref "R6") (pin "2") (pinfunction "2_2") (pintype "passive"))
    )
    (net (code "20") (name "Net-(LED5-PadC)") (class "Default")
      (node (ref "LED5") (pin "C") (pinfunction "C_C") (pintype "passive"))
      (node (ref "R18") (pin "2") (pinfunction "2_2") (pintype "passive"))
    )
    (net (code "21") (name "Net-(LED6-PadC)") (class "Default")
      (node (ref "LED6") (pin "C") (pinfunction "C_C") (pintype "passive"))
      (node (ref "R17") (pin "2") (pinfunction "2_2") (pintype "passive"))
    )
    (net (code "22") (name "Net-(LED7-PadC)") (class "Default")
      (node (ref "LED7") (pin "C") (pinfunction "C_C") (pintype "passive"))
      (node (ref "R16") (pin "2") (pinfunction "2_2") (pintype "passive"))
    )
    (net (code "23") (name "Net-(LED8-PadC)") (class "Default")
      (node (ref "LED8") (pin "C") (pinfunction "C_C") (pintype "passive"))
      (node (ref "R24") (pin "2") (pinfunction "2_2") (pintype "passive"))
    )
    (net (code "24") (name "Net-(Q1-G)") (class "Default")
      (node (ref "D1") (pin "A") (pinfunction "A_A") (pintype "passive"))
      (node (ref "Q1") (pin "1") (pinfunction "G_1") (pintype "passive"))
      (node (ref "R2") (pin "2") (pinfunction "2_2") (pintype "passive"))
    )
    (net (code "25") (name "Net-(Q3-PadB)") (class "Default")
      (node (ref "Q3") (pin "B") (pinfunction "B_B") (pintype "passive"))
      (node (ref "R23") (pin "2") (pinfunction "2_2") (pintype "passive"))
    )
    (net (code "26") (name "Net-(R21-S)") (class "Default")
      (node (ref "R21") (pin "2") (pinfunction "S_2") (pintype "passive"))
      (node (ref "U2") (pin "P7") (pinfunction "TRIM_P7") (pintype "bidirectional"))
    )
    (net (code "27") (name "Net-(U3-FILT)") (class "Default")
      (node (ref "C4") (pin "1") (pinfunction "1_1") (pintype "passive"))
      (node (ref "U3") (pin "6") (pinfunction "FILT_6") (pintype "bidirectional"))
    )
    (net (code "28") (name "Net-(U3-VOUT)") (class "Default")
      (node (ref "R14") (pin "1") (pinfunction "1_1") (pintype "passive"))
      (node (ref "U3") (pin "7") (pinfunction "VOUT_7") (pintype "bidirectional"))
    )
    (net (code "29") (name "Net-(U4-A)") (class "Default")
      (node (ref "R1") (pin "2") (pinfunction "2_2") (pintype "passive"))
      (node (ref "U4") (pin "1") (pinfunction "A_1") (pintype "passive"))
    )
    (net (code "30") (name "Net-(U4-COL)") (class "Default")
      (node (ref "R23") (pin "1") (pinfunction "1_1") (pintype "passive"))
      (node (ref "U4") (pin "4") (pinfunction "COL_4") (pintype "passive"))
    )
    (net (code "31") (name "Net-(U5-IN+)") (class "Default")
      (node (ref "R10") (pin "1") (pinfunction "1_1") (pintype "passive"))
      (node (ref "R11") (pin "2") (pinfunction "2_2") (pintype "passive"))
      (node (ref "U5") (pin "3") (pinfunction "IN+_3") (pintype "input"))
    )
    (net (code "32") (name "Net-(U5-IN-)") (class "Default")
      (node (ref "R12") (pin "2") (pinfunction "2_2") (pintype "passive"))
      (node (ref "R13") (pin "1") (pinfunction "1_1") (pintype "passive"))
      (node (ref "U5") (pin "4") (pinfunction "IN-_4") (pintype "input"))
    )
    (net (code "33") (name "Net-(U8-IN-)") (class "Default")
      (node (ref "R3") (pin "1") (pinfunction "1_1") (pintype "passive"))
      (node (ref "R4") (pin "2") (pinfunction "2_2") (pintype "passive"))
      (node (ref "U8") (pin "4") (pinfunction "IN-_4") (pintype "input"))
    )
    (net (code "34") (name "Net-(U8-OUT)") (class "Default")
      (node (ref "R6") (pin "1") (pinfunction "1_1") (pintype "passive"))
      (node (ref "U8") (pin "1") (pinfunction "OUT_1") (pintype "output"))
    )
    (net (code "35") (name "Net-(U9-IN-)") (class "Default")
      (node (ref "R4") (pin "1") (pinfunction "1_1") (pintype "passive"))
      (node (ref "R5") (pin "2") (pinfunction "2_2") (pintype "passive"))
      (node (ref "U9") (pin "4") (pinfunction "IN-_4") (pintype "input"))
    )
    (net (code "36") (name "Net-(U9-OUT)") (class "Default")
      (node (ref "R7") (pin "1") (pinfunction "1_1") (pintype "passive"))
      (node (ref "U9") (pin "1") (pinfunction "OUT_1") (pintype "output"))
    )
    (net (code "37") (name "RST") (class "Default")
      (node (ref "C15") (pin "1") (pinfunction "1_1") (pintype "passive"))
      (node (ref "J1") (pin "5") (pinfunction "5_5") (pintype "passive"))
      (node (ref "R15") (pin "1") (pinfunction "1_1") (pintype "passive"))
      (node (ref "S1") (pin "3") (pinfunction "3_3") (pintype "passive"))
      (node (ref "S1") (pin "4") (pinfunction "4_4") (pintype "passive"))
      (node (ref "U1") (pin "29") (pinfunction "PC6(/RESET)_29") (pintype "bidirectional"))
    )
    (net (code "38") (name "SCK") (class "Default")
      (node (ref "J1") (pin "3") (pinfunction "3_3") (pintype "passive"))
      (node (ref "U1") (pin "17") (pinfunction "PB5(SCK)_17") (pintype "bidirectional"))
    )
    (net (code "39") (name "SCL") (class "Default")
      (node (ref "P1") (pin "2") (pinfunction "P_2") (pintype "passive"))
      (node (ref "R19") (pin "1") (pinfunction "1_1") (pintype "passive"))
      (node (ref "U1") (pin "28") (pinfunction "PC5(ADC5/SCL)_28") (pintype "bidirectional"))
    )
    (net (code "40") (name "SDA") (class "Default")
      (node (ref "P1") (pin "1") (pinfunction "P_1") (pintype "passive"))
      (node (ref "R20") (pin "1") (pinfunction "1_1") (pintype "passive"))
      (node (ref "U1") (pin "27") (pinfunction "PC4(ADC4/SDA)_27") (pintype "bidirectional"))
    )
    (net (code "41") (name "TEMP") (class "Default")
      (node (ref "U6") (pin "2") (pinfunction "VO_2") (pintype "input"))
      (node (ref "U7") (pin "3") (pinfunction "IN+_3") (pintype "input"))
      (node (ref "U8") (pin "3") (pinfunction "IN+_3") (pintype "input"))
      (node (ref "U9") (pin "3") (pinfunction "IN+_3") (pintype "input"))
    )
    (net (code "42") (name "TEMP_OUT") (class "Default")
      (node (ref "U1") (pin "26") (pinfunction "PC3(ADC3)_26") (pintype "bidirectional"))
      (node (ref "U7") (pin "1") (pinfunction "OUT_1") (pintype "output"))
      (node (ref "U7") (pin "4") (pinfunction "IN-_4") (pintype "input"))
    )
    (net (code "43") (name "TEST1") (class "Default")
      (node (ref "LED6") (pin "A") (pinfunction "A_A") (pintype "passive"))
      (node (ref "U1") (pin "30") (pinfunction "PD0(RXD)_30") (pintype "bidirectional"))
    )
    (net (code "44") (name "TEST2") (class "Default")
      (node (ref "LED5") (pin "A") (pinfunction "A_A") (pintype "passive"))
      (node (ref "U1") (pin "31") (pinfunction "PD1(TXD)_31") (pintype "bidirectional"))
    )
    (net (code "45") (name "TEST3") (class "Default")
      (node (ref "LED7") (pin "A") (pinfunction "A_A") (pintype "passive"))
      (node (ref "U1") (pin "32") (pinfunction "PD2(INT0)_32") (pintype "bidirectional"))
    )
    (net (code "46") (name "V+") (class "Default")
      (node (ref "C2") (pin "1") (pinfunction "1_1") (pintype "passive"))
      (node (ref "C22") (pin "A") (pinfunction "+_A") (pintype "passive"))
      (node (ref "C23") (pin "A") (pinfunction "+_A") (pintype "passive"))
      (node (ref "R10") (pin "2") (pinfunction "2_2") (pintype "passive"))
      (node (ref "R21") (pin "1") (pinfunction "A_1") (pintype "passive"))
      (node (ref "R9") (pin "2") (pinfunction "2_2") (pintype "passive"))
      (node (ref "U2") (pin "P8") (pinfunction "SENSE+_P8") (pintype "bidirectional"))
      (node (ref "U2") (pin "P9") (pinfunction "VOUT_P9") (pintype "power_in"))
      (node (ref "U3") (pin "3") (pinfunction "IP-_3") (pintype "bidirectional"))
      (node (ref "U3") (pin "4") (pinfunction "IP-_4") (pintype "bidirectional"))
    )
    (net (code "47") (name "V24_MEA") (class "Default")
      (node (ref "R13") (pin "2") (pinfunction "2_2") (pintype "passive"))
      (node (ref "U1") (pin "23") (pinfunction "PC0(ADC0)_23") (pintype "bidirectional"))
      (node (ref "U5") (pin "1") (pinfunction "OUT_1") (pintype "output"))
    )
    (net (code "48") (name "VCC") (class "Default")
      (node (ref "Q1") (pin "3") (pinfunction "D_3") (pintype "passive"))
      (node (ref "X1") (pin "2") (pinfunction "S_2") (pintype "passive"))
    )
    (net (code "49") (name "unconnected-(Q2-OE-Pad1)") (class "Default")
      (node (ref "Q2") (pin "1") (pinfunction "OE_1") (pintype "input"))
    )
    (net (code "50") (name "unconnected-(U1-ADC6-Pad19)") (class "Default")
      (node (ref "U1") (pin "19") (pinfunction "ADC6_19") (pintype "bidirectional"))
    )
    (net (code "51") (name "unconnected-(U1-ADC7-Pad22)") (class "Default")
      (node (ref "U1") (pin "22") (pinfunction "ADC7_22") (pintype "bidirectional"))
    )
    (net (code "52") (name "unconnected-(U1-PB0(ICP)-Pad12)") (class "Default")
      (node (ref "U1") (pin "12") (pinfunction "PB0(ICP)_12") (pintype "bidirectional"))
    )
    (net (code "53") (name "unconnected-(U1-PB1(OC1A)-Pad13)") (class "Default")
      (node (ref "U1") (pin "13") (pinfunction "PB1(OC1A)_13") (pintype "bidirectional"))
    )
    (net (code "54") (name "unconnected-(U1-PB2(SS{slash}OC1B)-Pad14)") (class "Default")
      (node (ref "U1") (pin "14") (pinfunction "PB2(SS/OC1B)_14") (pintype "bidirectional"))
    )
    (net (code "55") (name "unconnected-(U1-PB7(XTAL2{slash}TOSC2)-Pad8)") (class "Default")
      (node (ref "U1") (pin "8") (pinfunction "PB7(XTAL2/TOSC2)_8") (pintype "bidirectional"))
    )
    (net (code "56") (name "unconnected-(U1-PC2(ADC2)-Pad25)") (class "Default")
      (node (ref "U1") (pin "25") (pinfunction "PC2(ADC2)_25") (pintype "bidirectional"))
    )
    (net (code "57") (name "unconnected-(U1-PD3(INT1)-Pad1)") (class "Default")
      (node (ref "U1") (pin "1") (pinfunction "PD3(INT1)_1") (pintype "bidirectional"))
    )
    (net (code "58") (name "unconnected-(U1-PD4(XCK{slash}T0)-Pad2)") (class "Default")
      (node (ref "U1") (pin "2") (pinfunction "PD4(XCK/T0)_2") (pintype "bidirectional"))
    )
    (net (code "59") (name "unconnected-(U1-PD6(AIN0)-Pad10)") (class "Default")
      (node (ref "U1") (pin "10") (pinfunction "PD6(AIN0)_10") (pintype "bidirectional"))
    )
    (net (code "60") (name "unconnected-(U1-PD7(AIN1)-Pad11)") (class "Default")
      (node (ref "U1") (pin "11") (pinfunction "PD7(AIN1)_11") (pintype "bidirectional"))
    )
    (net (code "61") (name "unconnected-(U2-CASE-PadP3)") (class "Default")
      (node (ref "U2") (pin "P3") (pinfunction "CASE_P3") (pintype "bidirectional"))
    )
  )
)
